# MIDI_Servo_Controller.net
KiCad netlist of a schematic drawn in EAGLE
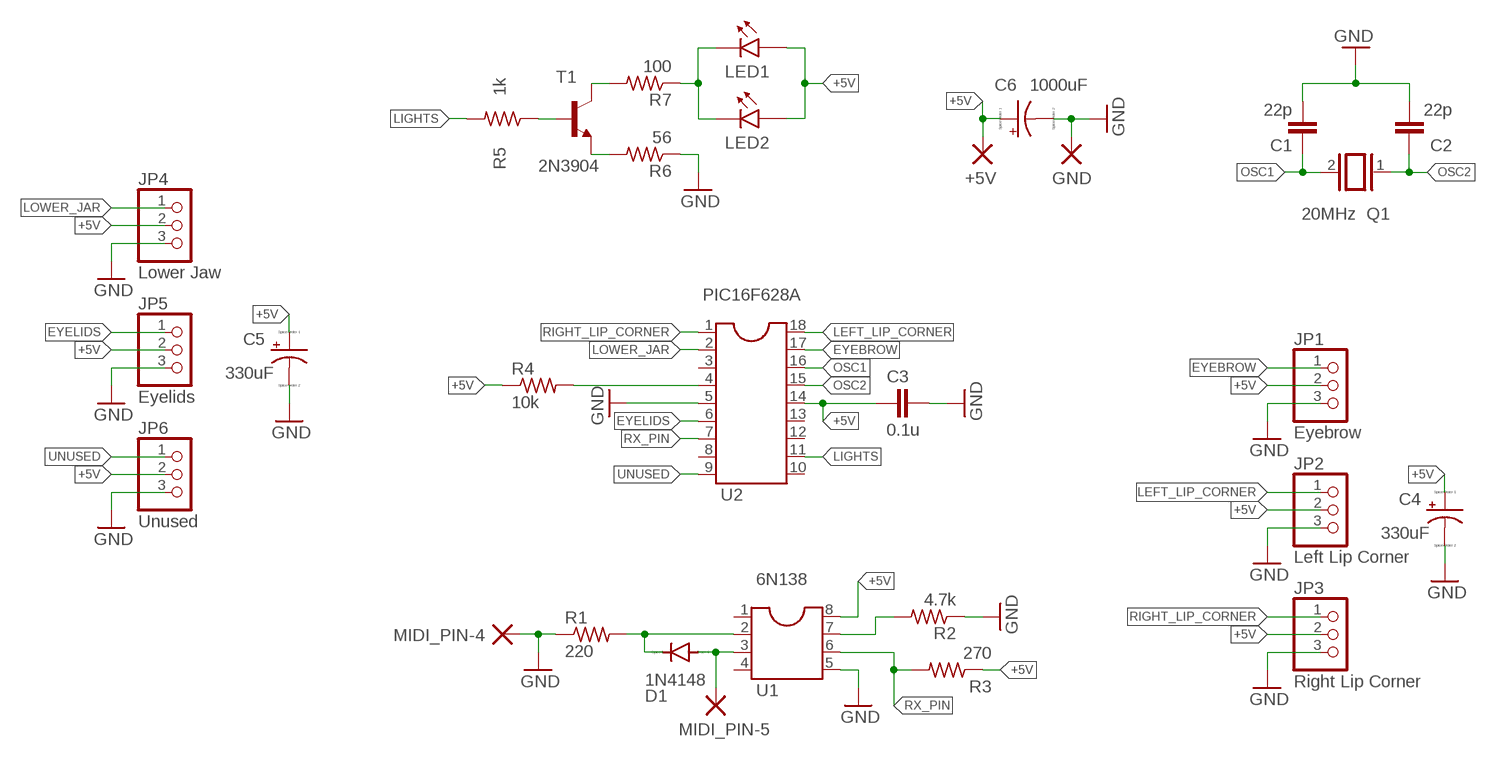
[diagram p0: schematic, sheet 1]

(export (version "E")
  (design (tool "Eeschema 10.0.6"))
  (components
    (comp (ref "+5V")
      (value "DOUBLE_THROUGH_HOLE_PAD")
      (footprint "eagle-import:DOUBLE_THROUGH_HOLE_PAD")
      (libsource (lib "eagle-import") (part "DOUBLE_THROUGH_HOLE_PAD"))
    )
    (comp (ref "6N138")
      (value "U1")
      (footprint "eagle-import:SOCKET-08")
      (libsource (lib "eagle-import") (part "DIL8S"))
    )
    (comp (ref "C1")
      (value "22p")
      (footprint "eagle-import:C050-025X075")
      (libsource (lib "eagle-import") (part "C-EU050-025X075"))
    )
    (comp (ref "C2")
      (value "22p")
      (footprint "eagle-import:C050-025X075")
      (libsource (lib "eagle-import") (part "C-EU050-025X075"))
    )
    (comp (ref "C3")
      (value "0.1u")
      (footprint "eagle-import:C050-025X075")
      (libsource (lib "eagle-import") (part "C-EU050-025X075"))
    )
    (comp (ref "C4")
      (value "330uF")
      (footprint "eagle-import:E3,5-8")
      (libsource (lib "eagle-import") (part "CPOL-USE3.5-8"))
    )
    (comp (ref "C5")
      (value "330uF")
      (footprint "eagle-import:E3,5-8")
      (libsource (lib "eagle-import") (part "CPOL-USE3.5-8"))
    )
    (comp (ref "C6")
      (value "1000uF")
      (footprint "eagle-import:E5-10,5")
      (libsource (lib "eagle-import") (part "CPOL-USE5-10.5"))
    )
    (comp (ref "D1")
      (value "1N4148")
      (footprint "eagle-import:DO35-10")
      (libsource (lib "eagle-import") (part "1N4148DO35-10"))
    )
    (comp (ref "GND")
      (value "DOUBLE_THROUGH_HOLE_PAD")
      (footprint "eagle-import:DOUBLE_THROUGH_HOLE_PAD")
      (libsource (lib "eagle-import") (part "DOUBLE_THROUGH_HOLE_PAD"))
    )
    (comp (ref "JP1")
      (value "Eyebrow")
      (footprint "eagle-import:1X03")
      (libsource (lib "eagle-import") (part "PINHD-1X3"))
    )
    (comp (ref "JP2")
      (value "Left Lip Corner")
      (footprint "eagle-import:1X03")
      (libsource (lib "eagle-import") (part "PINHD-1X3"))
    )
    (comp (ref "JP3")
      (value "Right Lip Corner")
      (footprint "eagle-import:1X03")
      (libsource (lib "eagle-import") (part "PINHD-1X3"))
    )
    (comp (ref "JP4")
      (value "Lower Jaw")
      (footprint "eagle-import:1X03")
      (libsource (lib "eagle-import") (part "PINHD-1X3"))
    )
    (comp (ref "JP5")
      (value "Eyelids")
      (footprint "eagle-import:1X03")
      (libsource (lib "eagle-import") (part "PINHD-1X3"))
    )
    (comp (ref "JP6")
      (value "Unused")
      (footprint "eagle-import:1X03")
      (libsource (lib "eagle-import") (part "PINHD-1X3"))
    )
    (comp (ref "LED1")
      (value "REMOTE_LED")
      (footprint "eagle-import:REMOTE_LED")
      (libsource (lib "eagle-import") (part "REMOTE_LED"))
    )
    (comp (ref "LED2")
      (value "REMOTE_LED")
      (footprint "eagle-import:REMOTE_LED")
      (libsource (lib "eagle-import") (part "REMOTE_LED"))
    )
    (comp (ref "MIDI_PIN-4")
      (value "DOUBLE_THROUGH_HOLE_PAD")
      (footprint "eagle-import:DOUBLE_THROUGH_HOLE_PAD")
      (libsource (lib "eagle-import") (part "DOUBLE_THROUGH_HOLE_PAD"))
    )
    (comp (ref "MIDI_PIN-5")
      (value "DOUBLE_THROUGH_HOLE_PAD")
      (footprint "eagle-import:DOUBLE_THROUGH_HOLE_PAD")
      (libsource (lib "eagle-import") (part "DOUBLE_THROUGH_HOLE_PAD"))
    )
    (comp (ref "PIC16F628A")
      (value "U2")
      (footprint "eagle-import:SOCKET-18")
      (libsource (lib "eagle-import") (part "DIL18S"))
    )
    (comp (ref "Q1")
      (value "20MHz")
      (footprint "eagle-import:QS")
      (libsource (lib "eagle-import") (part "XTAL/S"))
    )
    (comp (ref "R1")
      (value "220")
      (footprint "eagle-import:0207_12")
      (libsource (lib "eagle-import") (part "R-US_0207/12"))
    )
    (comp (ref "R2")
      (value "4.7k")
      (footprint "eagle-import:0207_12")
      (libsource (lib "eagle-import") (part "R-US_0207/12"))
    )
    (comp (ref "R3")
      (value "270")
      (footprint "eagle-import:0207_12")
      (libsource (lib "eagle-import") (part "R-US_0207/12"))
    )
    (comp (ref "R4")
      (value "10k")
      (footprint "eagle-import:0207_12")
      (libsource (lib "eagle-import") (part "R-US_0207/12"))
    )
    (comp (ref "R5")
      (value "1k")
      (footprint "eagle-import:0207_12")
      (libsource (lib "eagle-import") (part "R-US_0207/12"))
    )
    (comp (ref "R6")
      (value "56")
      (footprint "eagle-import:0207_12")
      (libsource (lib "eagle-import") (part "R-US_0207/12"))
    )
    (comp (ref "R7")
      (value "100")
      (footprint "eagle-import:0207_12")
      (libsource (lib "eagle-import") (part "R-US_0207/12"))
    )
    (comp (ref "T1")
      (value "2N3904")
      (footprint "eagle-import:TO92")
      (libsource (lib "eagle-import") (part "2N3904"))
    )
  )
  (nets
    (net (code "1") (name "+5V") (class "Default")
      (node (ref "+5V") (pin "P$1") (pinfunction "P$1_P$1") (pintype "bidirectional"))
      (node (ref "6N138") (pin "8") (pinfunction "8_8") (pintype "passive"))
      (node (ref "C3") (pin "2") (pinfunction "2_2") (pintype "passive"))
      (node (ref "C4") (pin "+") (pinfunction "+_+") (pintype "passive"))
      (node (ref "C5") (pin "+") (pinfunction "+_+") (pintype "passive"))
      (node (ref "C6") (pin "+") (pinfunction "+_+") (pintype "passive"))
      (node (ref "JP1") (pin "2") (pinfunction "2_2") (pintype "passive"))
      (node (ref "JP2") (pin "2") (pinfunction "2_2") (pintype "passive"))
      (node (ref "JP3") (pin "2") (pinfunction "2_2") (pintype "passive"))
      (node (ref "JP4") (pin "2") (pinfunction "2_2") (pintype "passive"))
      (node (ref "JP5") (pin "2") (pinfunction "2_2") (pintype "passive"))
      (node (ref "JP6") (pin "2") (pinfunction "2_2") (pintype "passive"))
      (node (ref "LED1") (pin "P$1") (pinfunction "P$1_P$1") (pintype "bidirectional"))
      (node (ref "LED2") (pin "P$1") (pinfunction "P$1_P$1") (pintype "bidirectional"))
      (node (ref "PIC16F628A") (pin "14") (pinfunction "14_14") (pintype "passive"))
      (node (ref "R3") (pin "1") (pinfunction "1_1") (pintype "passive"))
      (node (ref "R4") (pin "1") (pinfunction "1_1") (pintype "passive"))
    )
    (net (code "2") (name "EYEBROW") (class "Default")
      (node (ref "JP1") (pin "1") (pinfunction "1_1") (pintype "passive"))
      (node (ref "PIC16F628A") (pin "17") (pinfunction "17_17") (pintype "passive"))
    )
    (net (code "3") (name "EYELIDS") (class "Default")
      (node (ref "JP5") (pin "1") (pinfunction "1_1") (pintype "passive"))
      (node (ref "PIC16F628A") (pin "6") (pinfunction "6_6") (pintype "passive"))
    )
    (net (code "4") (name "GND") (class "Default")
      (node (ref "6N138") (pin "5") (pinfunction "5_5") (pintype "passive"))
      (node (ref "C1") (pin "2") (pinfunction "2_2") (pintype "passive"))
      (node (ref "C2") (pin "2") (pinfunction "2_2") (pintype "passive"))
      (node (ref "C3") (pin "1") (pinfunction "1_1") (pintype "passive"))
      (node (ref "C4") (pin "-") (pinfunction "-_-") (pintype "passive"))
      (node (ref "C5") (pin "-") (pinfunction "-_-") (pintype "passive"))
      (node (ref "C6") (pin "-") (pinfunction "-_-") (pintype "passive"))
      (node (ref "GND") (pin "P$1") (pinfunction "P$1_P$1") (pintype "bidirectional"))
      (node (ref "JP1") (pin "3") (pinfunction "3_3") (pintype "passive"))
      (node (ref "JP2") (pin "3") (pinfunction "3_3") (pintype "passive"))
      (node (ref "JP3") (pin "3") (pinfunction "3_3") (pintype "passive"))
      (node (ref "JP4") (pin "3") (pinfunction "3_3") (pintype "passive"))
      (node (ref "JP5") (pin "3") (pinfunction "3_3") (pintype "passive"))
      (node (ref "JP6") (pin "3") (pinfunction "3_3") (pintype "passive"))
      (node (ref "MIDI_PIN-4") (pin "P$1") (pinfunction "P$1_P$1") (pintype "bidirectional"))
      (node (ref "PIC16F628A") (pin "5") (pinfunction "5_5") (pintype "passive"))
      (node (ref "R1") (pin "1") (pinfunction "1_1") (pintype "passive"))
      (node (ref "R2") (pin "1") (pinfunction "1_1") (pintype "passive"))
      (node (ref "R6") (pin "1") (pinfunction "1_1") (pintype "passive"))
    )
    (net (code "5") (name "LEFT_LIP_CORNER") (class "Default")
      (node (ref "JP2") (pin "1") (pinfunction "1_1") (pintype "passive"))
      (node (ref "PIC16F628A") (pin "18") (pinfunction "18_18") (pintype "passive"))
    )
    (net (code "6") (name "LIGHTS") (class "Default")
      (node (ref "PIC16F628A") (pin "11") (pinfunction "11_11") (pintype "passive"))
      (node (ref "R5") (pin "2") (pinfunction "2_2") (pintype "passive"))
    )
    (net (code "7") (name "LOWER_JAR") (class "Default")
      (node (ref "JP4") (pin "1") (pinfunction "1_1") (pintype "passive"))
      (node (ref "PIC16F628A") (pin "2") (pinfunction "2_2") (pintype "passive"))
    )
    (net (code "8") (name "Net-(6N138-Pad2)") (class "Default")
      (node (ref "6N138") (pin "2") (pinfunction "2_2") (pintype "passive"))
      (node (ref "D1") (pin "C") (pinfunction "C_C") (pintype "passive"))
      (node (ref "R1") (pin "2") (pinfunction "2_2") (pintype "passive"))
    )
    (net (code "9") (name "Net-(6N138-Pad3)") (class "Default")
      (node (ref "6N138") (pin "3") (pinfunction "3_3") (pintype "passive"))
      (node (ref "D1") (pin "A") (pinfunction "A_A") (pintype "passive"))
      (node (ref "MIDI_PIN-5") (pin "P$1") (pinfunction "P$1_P$1") (pintype "bidirectional"))
    )
    (net (code "10") (name "Net-(6N138-Pad7)") (class "Default")
      (node (ref "6N138") (pin "7") (pinfunction "7_7") (pintype "passive"))
      (node (ref "R2") (pin "2") (pinfunction "2_2") (pintype "passive"))
    )
    (net (code "11") (name "Net-(LED1-PadP$2)") (class "Default")
      (node (ref "LED1") (pin "P$2") (pinfunction "P$2_P$2") (pintype "bidirectional"))
      (node (ref "LED2") (pin "P$2") (pinfunction "P$2_P$2") (pintype "bidirectional"))
      (node (ref "R7") (pin "1") (pinfunction "1_1") (pintype "passive"))
    )
    (net (code "12") (name "Net-(PIC16F628A-Pad4)") (class "Default")
      (node (ref "PIC16F628A") (pin "4") (pinfunction "4_4") (pintype "passive"))
      (node (ref "R4") (pin "2") (pinfunction "2_2") (pintype "passive"))
    )
    (net (code "13") (name "Net-(T1-B)") (class "Default")
      (node (ref "R5") (pin "1") (pinfunction "1_1") (pintype "passive"))
      (node (ref "T1") (pin "2") (pinfunction "B_2") (pintype "passive"))
    )
    (net (code "14") (name "Net-(T1-C)") (class "Default")
      (node (ref "R7") (pin "2") (pinfunction "2_2") (pintype "passive"))
      (node (ref "T1") (pin "1") (pinfunction "C_1") (pintype "passive"))
    )
    (net (code "15") (name "Net-(T1-E)") (class "Default")
      (node (ref "R6") (pin "2") (pinfunction "2_2") (pintype "passive"))
      (node (ref "T1") (pin "3") (pinfunction "E_3") (pintype "passive"))
    )
    (net (code "16") (name "OSC1") (class "Default")
      (node (ref "C1") (pin "1") (pinfunction "1_1") (pintype "passive"))
      (node (ref "PIC16F628A") (pin "16") (pinfunction "16_16") (pintype "passive"))
      (node (ref "Q1") (pin "2") (pinfunction "2_2") (pintype "passive"))
    )
    (net (code "17") (name "OSC2") (class "Default")
      (node (ref "C2") (pin "1") (pinfunction "1_1") (pintype "passive"))
      (node (ref "PIC16F628A") (pin "15") (pinfunction "15_15") (pintype "passive"))
      (node (ref "Q1") (pin "1") (pinfunction "1_1") (pintype "passive"))
    )
    (net (code "18") (name "RIGHT_LIP_CORNER") (class "Default")
      (node (ref "JP3") (pin "1") (pinfunction "1_1") (pintype "passive"))
      (node (ref "PIC16F628A") (pin "1") (pinfunction "1_1") (pintype "passive"))
    )
    (net (code "19") (name "RX_PIN") (class "Default")
      (node (ref "6N138") (pin "6") (pinfunction "6_6") (pintype "passive"))
      (node (ref "PIC16F628A") (pin "7") (pinfunction "7_7") (pintype "passive"))
      (node (ref "R3") (pin "2") (pinfunction "2_2") (pintype "passive"))
    )
    (net (code "20") (name "UNUSED") (class "Default")
      (node (ref "JP6") (pin "1") (pinfunction "1_1") (pintype "passive"))
      (node (ref "PIC16F628A") (pin "9") (pinfunction "9_9") (pintype "passive"))
    )
    (net (code "21") (name "unconnected-(6N138-Pad1)") (class "Default")
      (node (ref "6N138") (pin "1") (pinfunction "1_1") (pintype "passive"))
    )
    (net (code "22") (name "unconnected-(6N138-Pad4)") (class "Default")
      (node (ref "6N138") (pin "4") (pinfunction "4_4") (pintype "passive"))
    )
    (net (code "23") (name "unconnected-(PIC16F628A-Pad3)") (class "Default")
      (node (ref "PIC16F628A") (pin "3") (pinfunction "3_3") (pintype "passive"))
    )
    (net (code "24") (name "unconnected-(PIC16F628A-Pad8)") (class "Default")
      (node (ref "PIC16F628A") (pin "8") (pinfunction "8_8") (pintype "passive"))
    )
    (net (code "25") (name "unconnected-(PIC16F628A-Pad10)") (class "Default")
      (node (ref "PIC16F628A") (pin "10") (pinfunction "10_10") (pintype "passive"))
    )
    (net (code "26") (name "unconnected-(PIC16F628A-Pad12)") (class "Default")
      (node (ref "PIC16F628A") (pin "12") (pinfunction "12_12") (pintype "passive"))
    )
    (net (code "27") (name "unconnected-(PIC16F628A-Pad13)") (class "Default")
      (node (ref "PIC16F628A") (pin "13") (pinfunction "13_13") (pintype "passive"))
    )
  )
)
